# baseboard.net
KiCad netlist of a schematic drawn in EAGLE
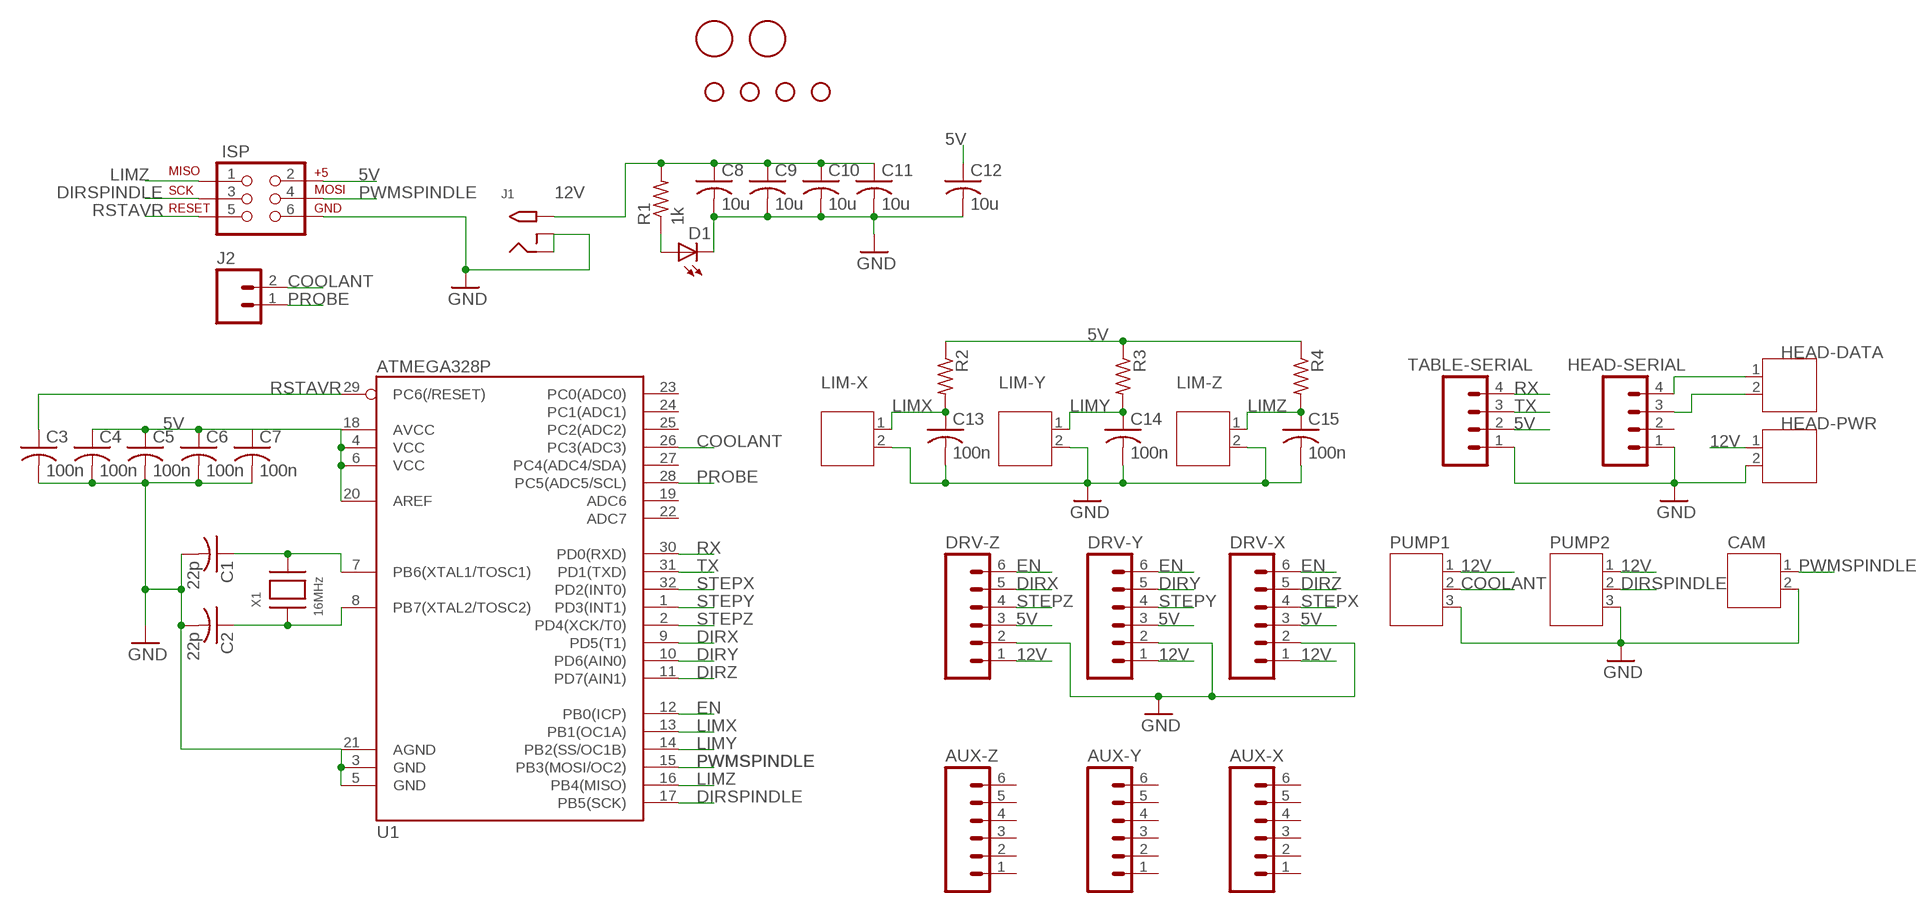
[diagram p0: schematic, sheet 1]

(export (version "E")
  (design (tool "Eeschema 10.0.6"))
  (components
    (comp (ref "AUX-X")
      (value "M06LOCK")
      (footprint "eagle-import:1X06_LOCK")
      (libsource (lib "eagle-import") (part "M06LOCK"))
    )
    (comp (ref "AUX-Y")
      (value "M06LOCK")
      (footprint "eagle-import:1X06_LOCK")
      (libsource (lib "eagle-import") (part "M06LOCK"))
    )
    (comp (ref "AUX-Z")
      (value "M06LOCK")
      (footprint "eagle-import:1X06_LOCK")
      (libsource (lib "eagle-import") (part "M06LOCK"))
    )
    (comp (ref "C1")
      (value "22p")
      (footprint "eagle-import:C0603")
      (libsource (lib "eagle-import") (part "C-USC0603"))
    )
    (comp (ref "C2")
      (value "22p")
      (footprint "eagle-import:C0603")
      (libsource (lib "eagle-import") (part "C-USC0603"))
    )
    (comp (ref "C3")
      (value "100n")
      (footprint "eagle-import:C0603")
      (libsource (lib "eagle-import") (part "C-USC0603"))
    )
    (comp (ref "C4")
      (value "100n")
      (footprint "eagle-import:C0603")
      (libsource (lib "eagle-import") (part "C-USC0603"))
    )
    (comp (ref "C5")
      (value "100n")
      (footprint "eagle-import:C0603")
      (libsource (lib "eagle-import") (part "C-USC0603"))
    )
    (comp (ref "C6")
      (value "100n")
      (footprint "eagle-import:C0603")
      (libsource (lib "eagle-import") (part "C-USC0603"))
    )
    (comp (ref "C7")
      (value "100n")
      (footprint "eagle-import:C0603")
      (libsource (lib "eagle-import") (part "C-USC0603"))
    )
    (comp (ref "C8")
      (value "10u")
      (footprint "eagle-import:C1206")
      (libsource (lib "eagle-import") (part "C-USC1206"))
    )
    (comp (ref "C9")
      (value "10u")
      (footprint "eagle-import:C1206")
      (libsource (lib "eagle-import") (part "C-USC1206"))
    )
    (comp (ref "C10")
      (value "10u")
      (footprint "eagle-import:C1206")
      (libsource (lib "eagle-import") (part "C-USC1206"))
    )
    (comp (ref "C11")
      (value "10u")
      (footprint "eagle-import:C1206")
      (libsource (lib "eagle-import") (part "C-USC1206"))
    )
    (comp (ref "C12")
      (value "10u")
      (footprint "eagle-import:C1206")
      (libsource (lib "eagle-import") (part "C-USC1206"))
    )
    (comp (ref "C13")
      (value "100n")
      (footprint "eagle-import:C0603")
      (libsource (lib "eagle-import") (part "C-USC0603"))
    )
    (comp (ref "C14")
      (value "100n")
      (footprint "eagle-import:C0603")
      (libsource (lib "eagle-import") (part "C-USC0603"))
    )
    (comp (ref "C15")
      (value "100n")
      (footprint "eagle-import:C0603")
      (libsource (lib "eagle-import") (part "C-USC0603"))
    )
    (comp (ref "CAM")
      (value "JST-PH2")
      (footprint "eagle-import:JST-PH2")
      (libsource (lib "eagle-import") (part "JST-PH2"))
    )
    (comp (ref "D1")
      (value "LEDCHIPLED_1206")
      (footprint "eagle-import:CHIPLED_1206")
      (libsource (lib "eagle-import") (part "LEDCHIPLED_1206"))
    )
    (comp (ref "DRV-X")
      (value "M06LOCK")
      (footprint "eagle-import:1X06_LOCK")
      (libsource (lib "eagle-import") (part "M06LOCK"))
    )
    (comp (ref "DRV-Y")
      (value "M06LOCK")
      (footprint "eagle-import:1X06_LOCK")
      (libsource (lib "eagle-import") (part "M06LOCK"))
    )
    (comp (ref "DRV-Z")
      (value "M06LOCK")
      (footprint "eagle-import:1X06_LOCK")
      (libsource (lib "eagle-import") (part "M06LOCK"))
    )
    (comp (ref "HEAD-DATA")
      (value "JST-PH2")
      (footprint "eagle-import:JST-PH2")
      (libsource (lib "eagle-import") (part "JST-PH2"))
    )
    (comp (ref "HEAD-PWR")
      (value "JST-PH2")
      (footprint "eagle-import:JST-PH2")
      (libsource (lib "eagle-import") (part "JST-PH2"))
    )
    (comp (ref "HEAD-SERIAL")
      (value "M04LOCK")
      (footprint "eagle-import:1X04_LOCK")
      (libsource (lib "eagle-import") (part "M04LOCK"))
    )
    (comp (ref "ISP")
      (value "AVR_SPI_PRG_6PTH")
      (footprint "eagle-import:2X3")
      (libsource (lib "eagle-import") (part "AVR_SPI_PRG_6PTH"))
    )
    (comp (ref "J1")
      (value "2.1MMJACKTHM")
      (footprint "eagle-import:PJ-102A")
      (libsource (lib "eagle-import") (part "2.1MMJACKTHM"))
    )
    (comp (ref "J2")
      (value "M02PTH")
      (footprint "eagle-import:1X02")
      (libsource (lib "eagle-import") (part "M02PTH"))
    )
    (comp (ref "LIM-X")
      (value "JST-PH2")
      (footprint "eagle-import:JST-PH2")
      (libsource (lib "eagle-import") (part "JST-PH2"))
    )
    (comp (ref "LIM-Y")
      (value "JST-PH2")
      (footprint "eagle-import:JST-PH2")
      (libsource (lib "eagle-import") (part "JST-PH2"))
    )
    (comp (ref "LIM-Z")
      (value "JST-PH2")
      (footprint "eagle-import:JST-PH2")
      (libsource (lib "eagle-import") (part "JST-PH2"))
    )
    (comp (ref "PUMP1")
      (value "JST-PH3")
      (footprint "eagle-import:JST-PH3")
      (libsource (lib "eagle-import") (part "JST-PH3"))
    )
    (comp (ref "PUMP2")
      (value "JST-PH3")
      (footprint "eagle-import:JST-PH3")
      (libsource (lib "eagle-import") (part "JST-PH3"))
    )
    (comp (ref "R1")
      (value "1k")
      (footprint "eagle-import:R1206")
      (libsource (lib "eagle-import") (part "R-US_R1206"))
    )
    (comp (ref "R2")
      (value "R-US_R0603")
      (footprint "eagle-import:R0603")
      (libsource (lib "eagle-import") (part "R-US_R0603"))
    )
    (comp (ref "R3")
      (value "R-US_R0603")
      (footprint "eagle-import:R0603")
      (libsource (lib "eagle-import") (part "R-US_R0603"))
    )
    (comp (ref "R4")
      (value "R-US_R0603")
      (footprint "eagle-import:R0603")
      (libsource (lib "eagle-import") (part "R-US_R0603"))
    )
    (comp (ref "STANDOFF1")
      (value "STAND-OFFTIGHT")
      (footprint "eagle-import:STAND-OFF-TIGHT")
      (libsource (lib "eagle-import") (part "STAND-OFFTIGHT"))
    )
    (comp (ref "STANDOFF2")
      (value "STAND-OFFTIGHT")
      (footprint "eagle-import:STAND-OFF-TIGHT")
      (libsource (lib "eagle-import") (part "STAND-OFFTIGHT"))
    )
    (comp (ref "STANDOFF3")
      (value "STAND-OFFTIGHT")
      (footprint "eagle-import:STAND-OFF-TIGHT")
      (libsource (lib "eagle-import") (part "STAND-OFFTIGHT"))
    )
    (comp (ref "STANDOFF4")
      (value "STAND-OFFTIGHT")
      (footprint "eagle-import:STAND-OFF-TIGHT")
      (libsource (lib "eagle-import") (part "STAND-OFFTIGHT"))
    )
    (comp (ref "TABLE-SERIAL")
      (value "M04LOCK")
      (footprint "eagle-import:1X04_LOCK")
      (libsource (lib "eagle-import") (part "M04LOCK"))
    )
    (comp (ref "U$1")
      (value "FIDUCIAL")
      (footprint "eagle-import:FIDUCIAL_1MM")
      (libsource (lib "eagle-import") (part "FIDUCIAL"))
    )
    (comp (ref "U$2")
      (value "FIDUCIAL")
      (footprint "eagle-import:FIDUCIAL_1MM")
      (libsource (lib "eagle-import") (part "FIDUCIAL"))
    )
    (comp (ref "U1")
      (value "ATMEGA328P")
      (footprint "eagle-import:TQFP32-08")
      (libsource (lib "eagle-import") (part "ATMEGA328_SMT"))
    )
    (comp (ref "X1")
      (value "16MHz")
      (footprint "eagle-import:XTAL3215")
      (libsource (lib "eagle-import") (part "XTAL-3.2X1.5"))
    )
  )
  (nets
    (net (code "1") (name "/5V") (class "Default")
      (node (ref "C12") (pin "1") (pinfunction "1_1") (pintype "passive"))
      (node (ref "C4") (pin "1") (pinfunction "1_1") (pintype "passive"))
      (node (ref "C5") (pin "1") (pinfunction "1_1") (pintype "passive"))
      (node (ref "C6") (pin "1") (pinfunction "1_1") (pintype "passive"))
      (node (ref "C7") (pin "1") (pinfunction "1_1") (pintype "passive"))
      (node (ref "DRV-X") (pin "3") (pinfunction "3_3") (pintype "passive"))
      (node (ref "DRV-Y") (pin "3") (pinfunction "3_3") (pintype "passive"))
      (node (ref "DRV-Z") (pin "3") (pinfunction "3_3") (pintype "passive"))
      (node (ref "ISP") (pin "2") (pinfunction "2_2") (pintype "passive"))
      (node (ref "R2") (pin "1") (pinfunction "1_1") (pintype "passive"))
      (node (ref "R3") (pin "1") (pinfunction "1_1") (pintype "passive"))
      (node (ref "R4") (pin "1") (pinfunction "1_1") (pintype "passive"))
      (node (ref "TABLE-SERIAL") (pin "2") (pinfunction "2_2") (pintype "passive"))
      (node (ref "U1") (pin "18") (pinfunction "AVCC_18") (pintype "bidirectional"))
      (node (ref "U1") (pin "20") (pinfunction "AREF_20") (pintype "bidirectional"))
      (node (ref "U1") (pin "4") (pinfunction "VCC_4") (pintype "bidirectional"))
      (node (ref "U1") (pin "6") (pinfunction "VCC_6") (pintype "bidirectional"))
    )
    (net (code "2") (name "/12V") (class "Default")
      (node (ref "C10") (pin "1") (pinfunction "1_1") (pintype "passive"))
      (node (ref "C11") (pin "1") (pinfunction "1_1") (pintype "passive"))
      (node (ref "C8") (pin "1") (pinfunction "1_1") (pintype "passive"))
      (node (ref "C9") (pin "1") (pinfunction "1_1") (pintype "passive"))
      (node (ref "DRV-X") (pin "1") (pinfunction "1_1") (pintype "passive"))
      (node (ref "DRV-Y") (pin "1") (pinfunction "1_1") (pintype "passive"))
      (node (ref "DRV-Z") (pin "1") (pinfunction "1_1") (pintype "passive"))
      (node (ref "HEAD-PWR") (pin "1") (pinfunction "1_1") (pintype "passive"))
      (node (ref "J1") (pin "TIP") (pinfunction "TIP_TIP") (pintype "bidirectional"))
      (node (ref "PUMP1") (pin "1") (pinfunction "1_1") (pintype "passive"))
      (node (ref "PUMP2") (pin "1") (pinfunction "1_1") (pintype "passive"))
      (node (ref "R1") (pin "2") (pinfunction "2_2") (pintype "passive"))
    )
    (net (code "3") (name "/COOLANT") (class "Default")
      (node (ref "J2") (pin "2") (pinfunction "2_2") (pintype "passive"))
      (node (ref "PUMP1") (pin "2") (pinfunction "2_2") (pintype "passive"))
      (node (ref "U1") (pin "26") (pinfunction "PC3(ADC3)_26") (pintype "bidirectional"))
    )
    (net (code "4") (name "/DIRSPINDLE") (class "Default")
      (node (ref "ISP") (pin "3") (pinfunction "3_3") (pintype "passive"))
      (node (ref "PUMP2") (pin "2") (pinfunction "2_2") (pintype "passive"))
      (node (ref "U1") (pin "17") (pinfunction "PB5(SCK)_17") (pintype "bidirectional"))
    )
    (net (code "5") (name "/DIRX") (class "Default")
      (node (ref "DRV-Z") (pin "5") (pinfunction "5_5") (pintype "passive"))
      (node (ref "U1") (pin "9") (pinfunction "PD5(T1)_9") (pintype "bidirectional"))
    )
    (net (code "6") (name "/DIRY") (class "Default")
      (node (ref "DRV-Y") (pin "5") (pinfunction "5_5") (pintype "passive"))
      (node (ref "U1") (pin "10") (pinfunction "PD6(AIN0)_10") (pintype "bidirectional"))
    )
    (net (code "7") (name "/DIRZ") (class "Default")
      (node (ref "DRV-X") (pin "5") (pinfunction "5_5") (pintype "passive"))
      (node (ref "U1") (pin "11") (pinfunction "PD7(AIN1)_11") (pintype "bidirectional"))
    )
    (net (code "8") (name "/EN") (class "Default")
      (node (ref "DRV-X") (pin "6") (pinfunction "6_6") (pintype "passive"))
      (node (ref "DRV-Y") (pin "6") (pinfunction "6_6") (pintype "passive"))
      (node (ref "DRV-Z") (pin "6") (pinfunction "6_6") (pintype "passive"))
      (node (ref "U1") (pin "12") (pinfunction "PB0(ICP)_12") (pintype "bidirectional"))
    )
    (net (code "9") (name "/LIMX") (class "Default")
      (node (ref "C13") (pin "1") (pinfunction "1_1") (pintype "passive"))
      (node (ref "LIM-X") (pin "1") (pinfunction "1_1") (pintype "passive"))
      (node (ref "R2") (pin "2") (pinfunction "2_2") (pintype "passive"))
      (node (ref "U1") (pin "13") (pinfunction "PB1(OC1A)_13") (pintype "bidirectional"))
    )
    (net (code "10") (name "/LIMY") (class "Default")
      (node (ref "C14") (pin "1") (pinfunction "1_1") (pintype "passive"))
      (node (ref "LIM-Y") (pin "1") (pinfunction "1_1") (pintype "passive"))
      (node (ref "R3") (pin "2") (pinfunction "2_2") (pintype "passive"))
      (node (ref "U1") (pin "14") (pinfunction "PB2(SS/OC1B)_14") (pintype "bidirectional"))
    )
    (net (code "11") (name "/LIMZ") (class "Default")
      (node (ref "C15") (pin "1") (pinfunction "1_1") (pintype "passive"))
      (node (ref "ISP") (pin "1") (pinfunction "1_1") (pintype "passive"))
      (node (ref "LIM-Z") (pin "1") (pinfunction "1_1") (pintype "passive"))
      (node (ref "R4") (pin "2") (pinfunction "2_2") (pintype "passive"))
      (node (ref "U1") (pin "16") (pinfunction "PB4(MISO)_16") (pintype "bidirectional"))
    )
    (net (code "12") (name "/PROBE") (class "Default")
      (node (ref "J2") (pin "1") (pinfunction "1_1") (pintype "passive"))
      (node (ref "U1") (pin "28") (pinfunction "PC5(ADC5/SCL)_28") (pintype "bidirectional"))
    )
    (net (code "13") (name "/PWMSPINDLE") (class "Default")
      (node (ref "CAM") (pin "1") (pinfunction "1_1") (pintype "passive"))
      (node (ref "ISP") (pin "4") (pinfunction "4_4") (pintype "passive"))
      (node (ref "U1") (pin "15") (pinfunction "PB3(MOSI/OC2)_15") (pintype "bidirectional"))
    )
    (net (code "14") (name "/RSTAVR") (class "Default")
      (node (ref "C3") (pin "1") (pinfunction "1_1") (pintype "passive"))
      (node (ref "ISP") (pin "5") (pinfunction "5_5") (pintype "passive"))
      (node (ref "U1") (pin "29") (pinfunction "PC6(/RESET)_29") (pintype "bidirectional"))
    )
    (net (code "15") (name "/RX") (class "Default")
      (node (ref "TABLE-SERIAL") (pin "4") (pinfunction "4_4") (pintype "passive"))
      (node (ref "U1") (pin "30") (pinfunction "PD0(RXD)_30") (pintype "bidirectional"))
    )
    (net (code "16") (name "/STEPX") (class "Default")
      (node (ref "DRV-X") (pin "4") (pinfunction "4_4") (pintype "passive"))
      (node (ref "U1") (pin "32") (pinfunction "PD2(INT0)_32") (pintype "bidirectional"))
    )
    (net (code "17") (name "/STEPY") (class "Default")
      (node (ref "DRV-Y") (pin "4") (pinfunction "4_4") (pintype "passive"))
      (node (ref "U1") (pin "1") (pinfunction "PD3(INT1)_1") (pintype "bidirectional"))
    )
    (net (code "18") (name "/STEPZ") (class "Default")
      (node (ref "DRV-Z") (pin "4") (pinfunction "4_4") (pintype "passive"))
      (node (ref "U1") (pin "2") (pinfunction "PD4(XCK/T0)_2") (pintype "bidirectional"))
    )
    (net (code "19") (name "/TX") (class "Default")
      (node (ref "TABLE-SERIAL") (pin "3") (pinfunction "3_3") (pintype "passive"))
      (node (ref "U1") (pin "31") (pinfunction "PD1(TXD)_31") (pintype "bidirectional"))
    )
    (net (code "20") (name "GND") (class "Default")
      (node (ref "C1") (pin "2") (pinfunction "2_2") (pintype "passive"))
      (node (ref "C10") (pin "2") (pinfunction "2_2") (pintype "passive"))
      (node (ref "C11") (pin "2") (pinfunction "2_2") (pintype "passive"))
      (node (ref "C12") (pin "2") (pinfunction "2_2") (pintype "passive"))
      (node (ref "C13") (pin "2") (pinfunction "2_2") (pintype "passive"))
      (node (ref "C14") (pin "2") (pinfunction "2_2") (pintype "passive"))
      (node (ref "C15") (pin "2") (pinfunction "2_2") (pintype "passive"))
      (node (ref "C2") (pin "2") (pinfunction "2_2") (pintype "passive"))
      (node (ref "C3") (pin "2") (pinfunction "2_2") (pintype "passive"))
      (node (ref "C4") (pin "2") (pinfunction "2_2") (pintype "passive"))
      (node (ref "C5") (pin "2") (pinfunction "2_2") (pintype "passive"))
      (node (ref "C6") (pin "2") (pinfunction "2_2") (pintype "passive"))
      (node (ref "C7") (pin "2") (pinfunction "2_2") (pintype "passive"))
      (node (ref "C8") (pin "2") (pinfunction "2_2") (pintype "passive"))
      (node (ref "C9") (pin "2") (pinfunction "2_2") (pintype "passive"))
      (node (ref "CAM") (pin "2") (pinfunction "2_2") (pintype "passive"))
      (node (ref "D1") (pin "C") (pinfunction "C_C") (pintype "passive"))
      (node (ref "DRV-X") (pin "2") (pinfunction "2_2") (pintype "passive"))
      (node (ref "DRV-Y") (pin "2") (pinfunction "2_2") (pintype "passive"))
      (node (ref "DRV-Z") (pin "2") (pinfunction "2_2") (pintype "passive"))
      (node (ref "HEAD-PWR") (pin "2") (pinfunction "2_2") (pintype "passive"))
      (node (ref "HEAD-SERIAL") (pin "1") (pinfunction "1_1") (pintype "passive"))
      (node (ref "ISP") (pin "6") (pinfunction "6_6") (pintype "passive"))
      (node (ref "J1") (pin "RING") (pinfunction "RING_RING") (pintype "bidirectional"))
      (node (ref "J1") (pin "RING_SW") (pinfunction "RING_SW_RING_SW") (pintype "bidirectional"))
      (node (ref "LIM-X") (pin "2") (pinfunction "2_2") (pintype "passive"))
      (node (ref "LIM-Y") (pin "2") (pinfunction "2_2") (pintype "passive"))
      (node (ref "LIM-Z") (pin "2") (pinfunction "2_2") (pintype "passive"))
      (node (ref "PUMP1") (pin "3") (pinfunction "3_3") (pintype "passive"))
      (node (ref "PUMP2") (pin "3") (pinfunction "3_3") (pintype "passive"))
      (node (ref "TABLE-SERIAL") (pin "1") (pinfunction "1_1") (pintype "passive"))
      (node (ref "U1") (pin "21") (pinfunction "AGND_21") (pintype "bidirectional"))
      (node (ref "U1") (pin "3") (pinfunction "GND_3") (pintype "bidirectional"))
      (node (ref "U1") (pin "5") (pinfunction "GND_5") (pintype "bidirectional"))
    )
    (net (code "21") (name "Net-(D1-PadA)") (class "Default")
      (node (ref "D1") (pin "A") (pinfunction "A_A") (pintype "passive"))
      (node (ref "R1") (pin "1") (pinfunction "1_1") (pintype "passive"))
    )
    (net (code "22") (name "Net-(HEAD-DATA-Pad1)") (class "Default")
      (node (ref "HEAD-DATA") (pin "1") (pinfunction "1_1") (pintype "passive"))
      (node (ref "HEAD-SERIAL") (pin "4") (pinfunction "4_4") (pintype "passive"))
    )
    (net (code "23") (name "Net-(HEAD-DATA-Pad2)") (class "Default")
      (node (ref "HEAD-DATA") (pin "2") (pinfunction "2_2") (pintype "passive"))
      (node (ref "HEAD-SERIAL") (pin "3") (pinfunction "3_3") (pintype "passive"))
    )
    (net (code "24") (name "Net-(U1-PB6(XTAL1{slash}TOSC1))") (class "Default")
      (node (ref "C1") (pin "1") (pinfunction "1_1") (pintype "passive"))
      (node (ref "U1") (pin "7") (pinfunction "PB6(XTAL1/TOSC1)_7") (pintype "bidirectional"))
      (node (ref "X1") (pin "P$2") (pinfunction "P$2_P$2") (pintype "bidirectional"))
    )
    (net (code "25") (name "Net-(U1-PB7(XTAL2{slash}TOSC2))") (class "Default")
      (node (ref "C2") (pin "1") (pinfunction "1_1") (pintype "passive"))
      (node (ref "U1") (pin "8") (pinfunction "PB7(XTAL2/TOSC2)_8") (pintype "bidirectional"))
      (node (ref "X1") (pin "P$1") (pinfunction "P$1_P$1") (pintype "bidirectional"))
    )
    (net (code "26") (name "unconnected-(AUX-X-Pad1)") (class "Default")
      (node (ref "AUX-X") (pin "1") (pinfunction "1_1") (pintype "passive"))
    )
    (net (code "27") (name "unconnected-(AUX-X-Pad2)") (class "Default")
      (node (ref "AUX-X") (pin "2") (pinfunction "2_2") (pintype "passive"))
    )
    (net (code "28") (name "unconnected-(AUX-X-Pad3)") (class "Default")
      (node (ref "AUX-X") (pin "3") (pinfunction "3_3") (pintype "passive"))
    )
    (net (code "29") (name "unconnected-(AUX-X-Pad4)") (class "Default")
      (node (ref "AUX-X") (pin "4") (pinfunction "4_4") (pintype "passive"))
    )
    (net (code "30") (name "unconnected-(AUX-X-Pad5)") (class "Default")
      (node (ref "AUX-X") (pin "5") (pinfunction "5_5") (pintype "passive"))
    )
    (net (code "31") (name "unconnected-(AUX-X-Pad6)") (class "Default")
      (node (ref "AUX-X") (pin "6") (pinfunction "6_6") (pintype "passive"))
    )
    (net (code "32") (name "unconnected-(AUX-Y-Pad1)") (class "Default")
      (node (ref "AUX-Y") (pin "1") (pinfunction "1_1") (pintype "passive"))
    )
    (net (code "33") (name "unconnected-(AUX-Y-Pad2)") (class "Default")
      (node (ref "AUX-Y") (pin "2") (pinfunction "2_2") (pintype "passive"))
    )
    (net (code "34") (name "unconnected-(AUX-Y-Pad3)") (class "Default")
      (node (ref "AUX-Y") (pin "3") (pinfunction "3_3") (pintype "passive"))
    )
    (net (code "35") (name "unconnected-(AUX-Y-Pad4)") (class "Default")
      (node (ref "AUX-Y") (pin "4") (pinfunction "4_4") (pintype "passive"))
    )
    (net (code "36") (name "unconnected-(AUX-Y-Pad5)") (class "Default")
      (node (ref "AUX-Y") (pin "5") (pinfunction "5_5") (pintype "passive"))
    )
    (net (code "37") (name "unconnected-(AUX-Y-Pad6)") (class "Default")
      (node (ref "AUX-Y") (pin "6") (pinfunction "6_6") (pintype "passive"))
    )
    (net (code "38") (name "unconnected-(AUX-Z-Pad1)") (class "Default")
      (node (ref "AUX-Z") (pin "1") (pinfunction "1_1") (pintype "passive"))
    )
    (net (code "39") (name "unconnected-(AUX-Z-Pad2)") (class "Default")
      (node (ref "AUX-Z") (pin "2") (pinfunction "2_2") (pintype "passive"))
    )
    (net (code "40") (name "unconnected-(AUX-Z-Pad3)") (class "Default")
      (node (ref "AUX-Z") (pin "3") (pinfunction "3_3") (pintype "passive"))
    )
    (net (code "41") (name "unconnected-(AUX-Z-Pad4)") (class "Default")
      (node (ref "AUX-Z") (pin "4") (pinfunction "4_4") (pintype "passive"))
    )
    (net (code "42") (name "unconnected-(AUX-Z-Pad5)") (class "Default")
      (node (ref "AUX-Z") (pin "5") (pinfunction "5_5") (pintype "passive"))
    )
    (net (code "43") (name "unconnected-(AUX-Z-Pad6)") (class "Default")
      (node (ref "AUX-Z") (pin "6") (pinfunction "6_6") (pintype "passive"))
    )
    (net (code "44") (name "unconnected-(HEAD-SERIAL-Pad2)") (class "Default")
      (node (ref "HEAD-SERIAL") (pin "2") (pinfunction "2_2") (pintype "passive"))
    )
    (net (code "45") (name "unconnected-(U1-ADC6-Pad19)") (class "Default")
      (node (ref "U1") (pin "19") (pinfunction "ADC6_19") (pintype "bidirectional"))
    )
    (net (code "46") (name "unconnected-(U1-ADC7-Pad22)") (class "Default")
      (node (ref "U1") (pin "22") (pinfunction "ADC7_22") (pintype "bidirectional"))
    )
    (net (code "47") (name "unconnected-(U1-PC0(ADC0)-Pad23)") (class "Default")
      (node (ref "U1") (pin "23") (pinfunction "PC0(ADC0)_23") (pintype "bidirectional"))
    )
    (net (code "48") (name "unconnected-(U1-PC1(ADC1)-Pad24)") (class "Default")
      (node (ref "U1") (pin "24") (pinfunction "PC1(ADC1)_24") (pintype "bidirectional"))
    )
    (net (code "49") (name "unconnected-(U1-PC2(ADC2)-Pad25)") (class "Default")
      (node (ref "U1") (pin "25") (pinfunction "PC2(ADC2)_25") (pintype "bidirectional"))
    )
    (net (code "50") (name "unconnected-(U1-PC4(ADC4{slash}SDA)-Pad27)") (class "Default")
      (node (ref "U1") (pin "27") (pinfunction "PC4(ADC4/SDA)_27") (pintype "bidirectional"))
    )
  )
)
